# PCB.net
KiCad netlist of a schematic drawn in EAGLE
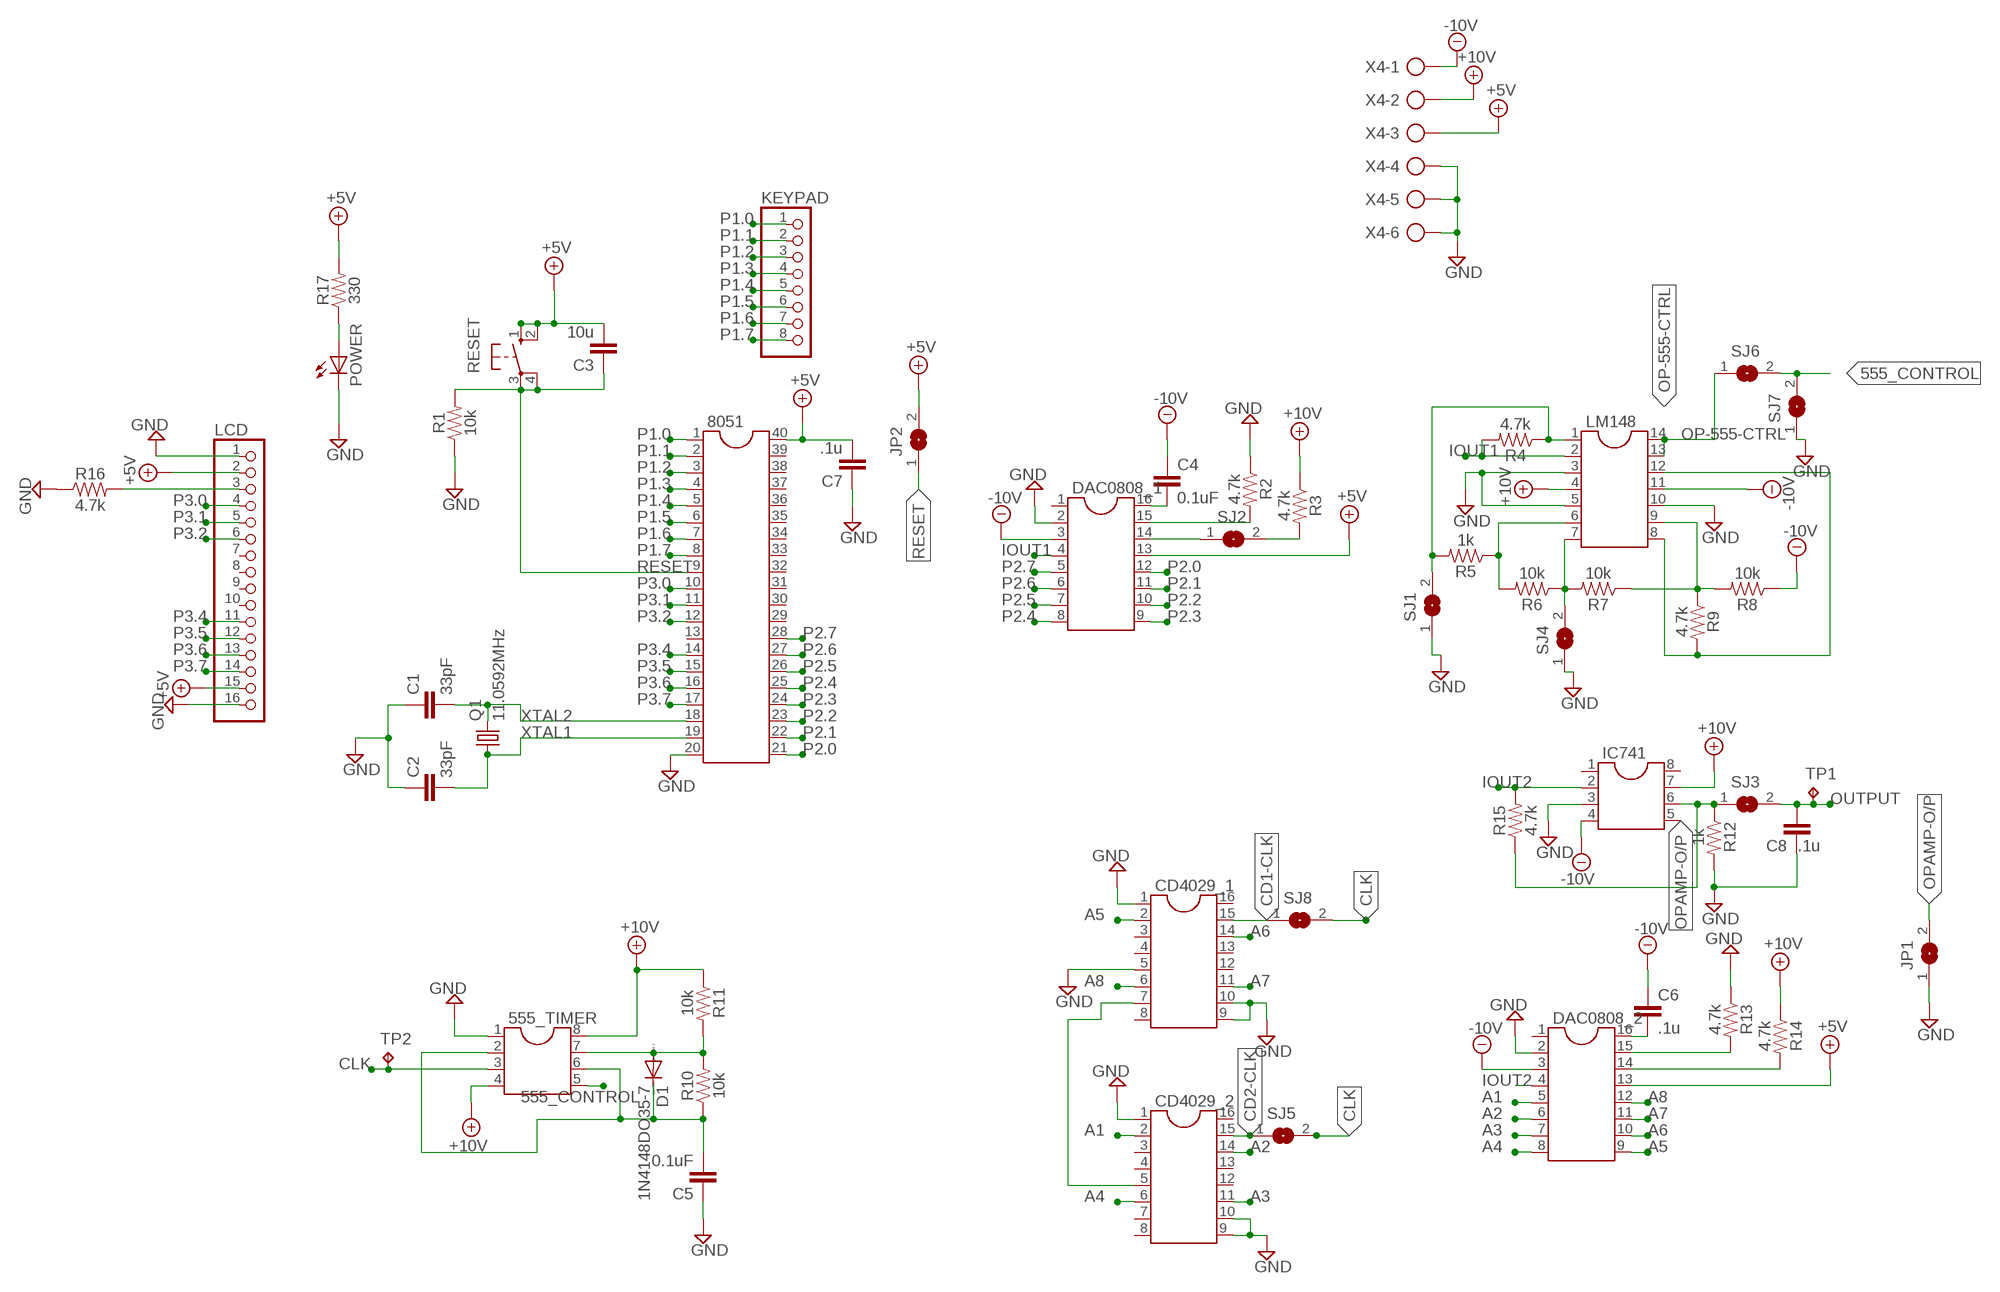
[diagram p0: schematic, sheet 1]

(export (version "E")
  (design (tool "Eeschema 10.0.6"))
  (components
    (comp (ref "555_TIMER")
      (value "DIL8")
      (footprint "eagle-import:DIL08")
      (libsource (lib "eagle-import") (part "DIL8"))
    )
    (comp (ref "8051")
      (value "DIL40")
      (footprint "eagle-import:DIL40")
      (fields (field (name "MF") "OLIMEX") (field (name "MPN") "PIC-USB-4550"))
      (libsource (lib "eagle-import") (part "DIL40"))
    )
    (comp (ref "C1")
      (value "33pF")
      (footprint "eagle-import:C025-025X050")
      (libsource (lib "eagle-import") (part "C-EU025-025X050"))
    )
    (comp (ref "C2")
      (value "33pF")
      (footprint "eagle-import:C025-025X050")
      (libsource (lib "eagle-import") (part "C-EU025-025X050"))
    )
    (comp (ref "C3")
      (value "10u")
      (footprint "eagle-import:C025-025X050")
      (libsource (lib "eagle-import") (part "C-EU025-025X050"))
    )
    (comp (ref "C4")
      (value "0.1uF")
      (footprint "eagle-import:C025-025X050")
      (libsource (lib "eagle-import") (part "C-EU025-025X050"))
    )
    (comp (ref "C5")
      (value "0.1uF")
      (footprint "eagle-import:C025-025X050")
      (libsource (lib "eagle-import") (part "C-EU025-025X050"))
    )
    (comp (ref "C6")
      (value ".1u")
      (footprint "eagle-import:C025-025X050")
      (libsource (lib "eagle-import") (part "C-EU025-025X050"))
    )
    (comp (ref "C7")
      (value ".1u")
      (footprint "eagle-import:C025-025X050")
      (libsource (lib "eagle-import") (part "C-EU025-025X050"))
    )
    (comp (ref "C8")
      (value ".1u")
      (footprint "eagle-import:C025-025X050")
      (libsource (lib "eagle-import") (part "C-EU025-025X050"))
    )
    (comp (ref "CD4029_1")
      (value "DIL16")
      (footprint "eagle-import:DIL16")
      (libsource (lib "eagle-import") (part "DIL16"))
    )
    (comp (ref "CD4029_2")
      (value "DIL16")
      (footprint "eagle-import:DIL16")
      (libsource (lib "eagle-import") (part "DIL16"))
    )
    (comp (ref "D1")
      (value "1N4148DO35-7")
      (footprint "eagle-import:DO35-7")
      (libsource (lib "eagle-import") (part "1N4148DO35-7"))
    )
    (comp (ref "DAC0808_1")
      (value "DIL16")
      (footprint "eagle-import:DIL16")
      (libsource (lib "eagle-import") (part "DIL16"))
    )
    (comp (ref "DAC0808_2")
      (value "DIL16")
      (footprint "eagle-import:DIL16")
      (libsource (lib "eagle-import") (part "DIL16"))
    )
    (comp (ref "IC741")
      (value "DIL8")
      (footprint "eagle-import:DIL08")
      (libsource (lib "eagle-import") (part "DIL8"))
    )
    (comp (ref "JP1") (value "SJ") (footprint "eagle-import:SJ") (libsource (lib "eagle-import") (part "SJ")))
    (comp (ref "JP2") (value "SJ") (footprint "eagle-import:SJ") (libsource (lib "eagle-import") (part "SJ")))
    (comp (ref "KEYPAD")
      (value "PINHD-1X8")
      (footprint "eagle-import:1X08")
      (libsource (lib "eagle-import") (part "PINHD-1X8"))
    )
    (comp (ref "LCD")
      (value "PINHD-1X16")
      (footprint "eagle-import:1X16")
      (libsource (lib "eagle-import") (part "PINHD-1X16"))
    )
    (comp (ref "LM148")
      (value "DIL14")
      (footprint "eagle-import:DIL14")
      (libsource (lib "eagle-import") (part "DIL14"))
    )
    (comp (ref "POWER")
      (value "LED5MM")
      (footprint "eagle-import:LED5MM")
      (libsource (lib "eagle-import") (part "LED5MM"))
    )
    (comp (ref "Q1")
      (value "11.0592MHz")
      (footprint "eagle-import:HC49_S")
      (fields (field (name "MF") "MULTICOMP") (field (name "MPN") "HC49SM-3.6864-30-50-60-16-ATF"))
      (libsource (lib "eagle-import") (part "CRYSTALHC49S"))
    )
    (comp (ref "R1")
      (value "10k")
      (footprint "eagle-import:AXIAL-0.3")
      (libsource (lib "eagle-import") (part "RESISTORAXIAL-0.3"))
    )
    (comp (ref "R2")
      (value "4.7k")
      (footprint "eagle-import:AXIAL-0.3")
      (libsource (lib "eagle-import") (part "RESISTORAXIAL-0.3"))
    )
    (comp (ref "R3")
      (value "4.7k")
      (footprint "eagle-import:AXIAL-0.3")
      (libsource (lib "eagle-import") (part "RESISTORAXIAL-0.3"))
    )
    (comp (ref "R4")
      (value "4.7k")
      (footprint "eagle-import:AXIAL-0.3")
      (libsource (lib "eagle-import") (part "RESISTORAXIAL-0.3"))
    )
    (comp (ref "R5")
      (value "1k")
      (footprint "eagle-import:AXIAL-0.3")
      (libsource (lib "eagle-import") (part "RESISTORAXIAL-0.3"))
    )
    (comp (ref "R6")
      (value "10k")
      (footprint "eagle-import:AXIAL-0.3")
      (libsource (lib "eagle-import") (part "RESISTORAXIAL-0.3"))
    )
    (comp (ref "R7")
      (value "10k")
      (footprint "eagle-import:AXIAL-0.3")
      (libsource (lib "eagle-import") (part "RESISTORAXIAL-0.3"))
    )
    (comp (ref "R8")
      (value "10k")
      (footprint "eagle-import:AXIAL-0.3")
      (libsource (lib "eagle-import") (part "RESISTORAXIAL-0.3"))
    )
    (comp (ref "R9")
      (value "4.7k")
      (footprint "eagle-import:AXIAL-0.3")
      (libsource (lib "eagle-import") (part "RESISTORAXIAL-0.3"))
    )
    (comp (ref "R10")
      (value "10k")
      (footprint "eagle-import:AXIAL-0.3")
      (libsource (lib "eagle-import") (part "RESISTORAXIAL-0.3"))
    )
    (comp (ref "R11")
      (value "10k")
      (footprint "eagle-import:AXIAL-0.3")
      (libsource (lib "eagle-import") (part "RESISTORAXIAL-0.3"))
    )
    (comp (ref "R12")
      (value "1k")
      (footprint "eagle-import:AXIAL-0.3")
      (libsource (lib "eagle-import") (part "RESISTORAXIAL-0.3"))
    )
    (comp (ref "R13")
      (value "4.7k")
      (footprint "eagle-import:AXIAL-0.3")
      (libsource (lib "eagle-import") (part "RESISTORAXIAL-0.3"))
    )
    (comp (ref "R14")
      (value "4.7k")
      (footprint "eagle-import:AXIAL-0.3")
      (libsource (lib "eagle-import") (part "RESISTORAXIAL-0.3"))
    )
    (comp (ref "R15")
      (value "4.7k")
      (footprint "eagle-import:AXIAL-0.3")
      (libsource (lib "eagle-import") (part "RESISTORAXIAL-0.3"))
    )
    (comp (ref "R16")
      (value "4.7k")
      (footprint "eagle-import:AXIAL-0.3")
      (libsource (lib "eagle-import") (part "RESISTORAXIAL-0.3"))
    )
    (comp (ref "R17")
      (value "330")
      (footprint "eagle-import:AXIAL-0.3")
      (libsource (lib "eagle-import") (part "RESISTORAXIAL-0.3"))
    )
    (comp (ref "RESET")
      (value "10-XX")
      (footprint "eagle-import:B3F-10XX")
      (fields (field (name "MPN") "B3F-1000") (field (name "MF") "OMRON"))
      (libsource (lib "eagle-import") (part "10-XX"))
    )
    (comp (ref "SJ1") (value "SJ") (footprint "eagle-import:SJ") (libsource (lib "eagle-import") (part "SJ")))
    (comp (ref "SJ2") (value "SJ") (footprint "eagle-import:SJ") (libsource (lib "eagle-import") (part "SJ")))
    (comp (ref "SJ3") (value "SJ") (footprint "eagle-import:SJ") (libsource (lib "eagle-import") (part "SJ")))
    (comp (ref "SJ4") (value "SJ") (footprint "eagle-import:SJ") (libsource (lib "eagle-import") (part "SJ")))
    (comp (ref "SJ5") (value "SJ") (footprint "eagle-import:SJ") (libsource (lib "eagle-import") (part "SJ")))
    (comp (ref "SJ6") (value "SJ") (footprint "eagle-import:SJ") (libsource (lib "eagle-import") (part "SJ")))
    (comp (ref "SJ7") (value "SJ") (footprint "eagle-import:SJ") (libsource (lib "eagle-import") (part "SJ")))
    (comp (ref "SJ8") (value "SJ") (footprint "eagle-import:SJ") (libsource (lib "eagle-import") (part "SJ")))
    (comp (ref "TP1")
      (value "TPPAD1-20")
      (footprint "eagle-import:P1-20")
      (libsource (lib "eagle-import") (part "TPPAD1-20"))
    )
    (comp (ref "TP2")
      (value "TPPAD1-20")
      (footprint "eagle-import:P1-20")
      (libsource (lib "eagle-import") (part "TPPAD1-20"))
    )
    (comp (ref "X4")
      (value "AK500/6-H")
      (footprint "eagle-import:AK500_6-H")
      (fields (field (name "OC_FARNELL") "unknown"))
      (libsource (lib "eagle-import") (part "AK500/6-H"))
    )
  )
  (nets
    (net (code "1") (name "+5V") (class "Default")
      (node (ref "8051") (pin "40") (pinfunction "40_40") (pintype "passive"))
      (node (ref "C3") (pin "2") (pinfunction "2_2") (pintype "passive"))
      (node (ref "C7") (pin "2") (pinfunction "2_2") (pintype "passive"))
      (node (ref "DAC0808_1") (pin "13") (pinfunction "13_13") (pintype "passive"))
      (node (ref "DAC0808_2") (pin "13") (pinfunction "13_13") (pintype "passive"))
      (node (ref "JP2") (pin "2") (pinfunction "2_2") (pintype "passive"))
      (node (ref "LCD") (pin "15") (pinfunction "15_15") (pintype "passive"))
      (node (ref "LCD") (pin "2") (pinfunction "2_2") (pintype "passive"))
      (node (ref "R17") (pin "P$2") (pinfunction "2_P$2") (pintype "passive"))
      (node (ref "RESET") (pin "1") (pinfunction "S_1") (pintype "passive"))
      (node (ref "RESET") (pin "2") (pinfunction "S1_2") (pintype "passive"))
      (node (ref "X4") (pin "3") (pinfunction "KL_3") (pintype "passive"))
    )
    (net (code "2") (name "+10V") (class "Default")
      (node (ref "555_TIMER") (pin "4") (pinfunction "4_4") (pintype "passive"))
      (node (ref "555_TIMER") (pin "8") (pinfunction "8_8") (pintype "passive"))
      (node (ref "IC741") (pin "7") (pinfunction "7_7") (pintype "passive"))
      (node (ref "LM148") (pin "4") (pinfunction "4_4") (pintype "passive"))
      (node (ref "R11") (pin "P$1") (pinfunction "1_P$1") (pintype "passive"))
      (node (ref "R14") (pin "P$1") (pinfunction "1_P$1") (pintype "passive"))
      (node (ref "R3") (pin "P$1") (pinfunction "1_P$1") (pintype "passive"))
      (node (ref "X4") (pin "2") (pinfunction "KL_2") (pintype "passive"))
    )
    (net (code "3") (name "-10V") (class "Default")
      (node (ref "C4") (pin "1") (pinfunction "1_1") (pintype "passive"))
      (node (ref "C6") (pin "1") (pinfunction "1_1") (pintype "passive"))
      (node (ref "DAC0808_1") (pin "3") (pinfunction "3_3") (pintype "passive"))
      (node (ref "DAC0808_2") (pin "3") (pinfunction "3_3") (pintype "passive"))
      (node (ref "IC741") (pin "4") (pinfunction "4_4") (pintype "passive"))
      (node (ref "LM148") (pin "11") (pinfunction "11_11") (pintype "passive"))
      (node (ref "R8") (pin "P$1") (pinfunction "1_P$1") (pintype "passive"))
      (node (ref "X4") (pin "1") (pinfunction "KL_1") (pintype "passive"))
    )
    (net (code "4") (name "/A1") (class "Default")
      (node (ref "CD4029_2") (pin "2") (pinfunction "2_2") (pintype "passive"))
      (node (ref "DAC0808_2") (pin "5") (pinfunction "5_5") (pintype "passive"))
    )
    (net (code "5") (name "/A2") (class "Default")
      (node (ref "CD4029_2") (pin "14") (pinfunction "14_14") (pintype "passive"))
      (node (ref "DAC0808_2") (pin "6") (pinfunction "6_6") (pintype "passive"))
    )
    (net (code "6") (name "/A3") (class "Default")
      (node (ref "CD4029_2") (pin "11") (pinfunction "11_11") (pintype "passive"))
      (node (ref "DAC0808_2") (pin "7") (pinfunction "7_7") (pintype "passive"))
    )
    (net (code "7") (name "/A4") (class "Default")
      (node (ref "CD4029_2") (pin "6") (pinfunction "6_6") (pintype "passive"))
      (node (ref "DAC0808_2") (pin "8") (pinfunction "8_8") (pintype "passive"))
    )
    (net (code "8") (name "/A5") (class "Default")
      (node (ref "CD4029_1") (pin "2") (pinfunction "2_2") (pintype "passive"))
      (node (ref "DAC0808_2") (pin "9") (pinfunction "9_9") (pintype "passive"))
    )
    (net (code "9") (name "/A6") (class "Default")
      (node (ref "CD4029_1") (pin "14") (pinfunction "14_14") (pintype "passive"))
      (node (ref "DAC0808_2") (pin "10") (pinfunction "10_10") (pintype "passive"))
    )
    (net (code "10") (name "/A7") (class "Default")
      (node (ref "CD4029_1") (pin "11") (pinfunction "11_11") (pintype "passive"))
      (node (ref "DAC0808_2") (pin "11") (pinfunction "11_11") (pintype "passive"))
    )
    (net (code "11") (name "/A8") (class "Default")
      (node (ref "CD4029_1") (pin "6") (pinfunction "6_6") (pintype "passive"))
      (node (ref "DAC0808_2") (pin "12") (pinfunction "12_12") (pintype "passive"))
    )
    (net (code "12") (name "/IOUT1") (class "Default")
      (node (ref "DAC0808_1") (pin "4") (pinfunction "4_4") (pintype "passive"))
      (node (ref "LM148") (pin "2") (pinfunction "2_2") (pintype "passive"))
      (node (ref "R4") (pin "P$2") (pinfunction "2_P$2") (pintype "passive"))
    )
    (net (code "13") (name "/IOUT2") (class "Default")
      (node (ref "DAC0808_2") (pin "4") (pinfunction "4_4") (pintype "passive"))
      (node (ref "IC741") (pin "2") (pinfunction "2_2") (pintype "passive"))
      (node (ref "R15") (pin "P$2") (pinfunction "2_P$2") (pintype "passive"))
    )
    (net (code "14") (name "/OUTPUT") (class "Default")
      (node (ref "C8") (pin "2") (pinfunction "2_2") (pintype "passive"))
      (node (ref "SJ3") (pin "2") (pinfunction "2_2") (pintype "passive"))
      (node (ref "TP1") (pin "TP") (pinfunction "TP_TP") (pintype "input"))
    )
    (net (code "15") (name "/P1.0") (class "Default")
      (node (ref "8051") (pin "1") (pinfunction "1_1") (pintype "passive"))
      (node (ref "KEYPAD") (pin "1") (pinfunction "1_1") (pintype "passive"))
    )
    (net (code "16") (name "/P1.1") (class "Default")
      (node (ref "8051") (pin "2") (pinfunction "2_2") (pintype "passive"))
      (node (ref "KEYPAD") (pin "2") (pinfunction "2_2") (pintype "passive"))
    )
    (net (code "17") (name "/P1.2") (class "Default")
      (node (ref "8051") (pin "3") (pinfunction "3_3") (pintype "passive"))
      (node (ref "KEYPAD") (pin "3") (pinfunction "3_3") (pintype "passive"))
    )
    (net (code "18") (name "/P1.3") (class "Default")
      (node (ref "8051") (pin "4") (pinfunction "4_4") (pintype "passive"))
      (node (ref "KEYPAD") (pin "4") (pinfunction "4_4") (pintype "passive"))
    )
    (net (code "19") (name "/P1.4") (class "Default")
      (node (ref "8051") (pin "5") (pinfunction "5_5") (pintype "passive"))
      (node (ref "KEYPAD") (pin "5") (pinfunction "5_5") (pintype "passive"))
    )
    (net (code "20") (name "/P1.5") (class "Default")
      (node (ref "8051") (pin "6") (pinfunction "6_6") (pintype "passive"))
      (node (ref "KEYPAD") (pin "6") (pinfunction "6_6") (pintype "passive"))
    )
    (net (code "21") (name "/P1.6") (class "Default")
      (node (ref "8051") (pin "7") (pinfunction "7_7") (pintype "passive"))
      (node (ref "KEYPAD") (pin "7") (pinfunction "7_7") (pintype "passive"))
    )
    (net (code "22") (name "/P1.7") (class "Default")
      (node (ref "8051") (pin "8") (pinfunction "8_8") (pintype "passive"))
      (node (ref "KEYPAD") (pin "8") (pinfunction "8_8") (pintype "passive"))
    )
    (net (code "23") (name "/P2.0") (class "Default")
      (node (ref "8051") (pin "21") (pinfunction "21_21") (pintype "passive"))
      (node (ref "DAC0808_1") (pin "12") (pinfunction "12_12") (pintype "passive"))
    )
    (net (code "24") (name "/P2.1") (class "Default")
      (node (ref "8051") (pin "22") (pinfunction "22_22") (pintype "passive"))
      (node (ref "DAC0808_1") (pin "11") (pinfunction "11_11") (pintype "passive"))
    )
    (net (code "25") (name "/P2.2") (class "Default")
      (node (ref "8051") (pin "23") (pinfunction "23_23") (pintype "passive"))
      (node (ref "DAC0808_1") (pin "10") (pinfunction "10_10") (pintype "passive"))
    )
    (net (code "26") (name "/P2.3") (class "Default")
      (node (ref "8051") (pin "24") (pinfunction "24_24") (pintype "passive"))
      (node (ref "DAC0808_1") (pin "9") (pinfunction "9_9") (pintype "passive"))
    )
    (net (code "27") (name "/P2.4") (class "Default")
      (node (ref "8051") (pin "25") (pinfunction "25_25") (pintype "passive"))
      (node (ref "DAC0808_1") (pin "8") (pinfunction "8_8") (pintype "passive"))
    )
    (net (code "28") (name "/P2.5") (class "Default")
      (node (ref "8051") (pin "26") (pinfunction "26_26") (pintype "passive"))
      (node (ref "DAC0808_1") (pin "7") (pinfunction "7_7") (pintype "passive"))
    )
    (net (code "29") (name "/P2.6") (class "Default")
      (node (ref "8051") (pin "27") (pinfunction "27_27") (pintype "passive"))
      (node (ref "DAC0808_1") (pin "6") (pinfunction "6_6") (pintype "passive"))
    )
    (net (code "30") (name "/P2.7") (class "Default")
      (node (ref "8051") (pin "28") (pinfunction "28_28") (pintype "passive"))
      (node (ref "DAC0808_1") (pin "5") (pinfunction "5_5") (pintype "passive"))
    )
    (net (code "31") (name "/P3.0") (class "Default")
      (node (ref "8051") (pin "10") (pinfunction "10_10") (pintype "passive"))
      (node (ref "LCD") (pin "4") (pinfunction "4_4") (pintype "passive"))
    )
    (net (code "32") (name "/P3.1") (class "Default")
      (node (ref "8051") (pin "11") (pinfunction "11_11") (pintype "passive"))
      (node (ref "LCD") (pin "5") (pinfunction "5_5") (pintype "passive"))
    )
    (net (code "33") (name "/P3.2") (class "Default")
      (node (ref "8051") (pin "12") (pinfunction "12_12") (pintype "passive"))
      (node (ref "LCD") (pin "6") (pinfunction "6_6") (pintype "passive"))
    )
    (net (code "34") (name "/P3.4") (class "Default")
      (node (ref "8051") (pin "14") (pinfunction "14_14") (pintype "passive"))
      (node (ref "LCD") (pin "11") (pinfunction "11_11") (pintype "passive"))
    )
    (net (code "35") (name "/P3.5") (class "Default")
      (node (ref "8051") (pin "15") (pinfunction "15_15") (pintype "passive"))
      (node (ref "LCD") (pin "12") (pinfunction "12_12") (pintype "passive"))
    )
    (net (code "36") (name "/P3.6") (class "Default")
      (node (ref "8051") (pin "16") (pinfunction "16_16") (pintype "passive"))
      (node (ref "LCD") (pin "13") (pinfunction "13_13") (pintype "passive"))
    )
    (net (code "37") (name "/P3.7") (class "Default")
      (node (ref "8051") (pin "17") (pinfunction "17_17") (pintype "passive"))
      (node (ref "LCD") (pin "14") (pinfunction "14_14") (pintype "passive"))
    )
    (net (code "38") (name "/XTAL1") (class "Default")
      (node (ref "8051") (pin "19") (pinfunction "19_19") (pintype "passive"))
      (node (ref "C2") (pin "2") (pinfunction "2_2") (pintype "passive"))
      (node (ref "Q1") (pin "1") (pinfunction "1_1") (pintype "passive"))
    )
    (net (code "39") (name "/XTAL2") (class "Default")
      (node (ref "8051") (pin "18") (pinfunction "18_18") (pintype "passive"))
      (node (ref "C1") (pin "2") (pinfunction "2_2") (pintype "passive"))
      (node (ref "Q1") (pin "2") (pinfunction "2_2") (pintype "passive"))
    )
    (net (code "40") (name "555_CONTROL") (class "Default")
      (node (ref "555_TIMER") (pin "5") (pinfunction "5_5") (pintype "passive"))
      (node (ref "SJ6") (pin "2") (pinfunction "2_2") (pintype "passive"))
      (node (ref "SJ7") (pin "2") (pinfunction "2_2") (pintype "passive"))
    )
    (net (code "41") (name "CD1-CLK") (class "Default")
      (node (ref "CD4029_1") (pin "15") (pinfunction "15_15") (pintype "passive"))
      (node (ref "SJ8") (pin "1") (pinfunction "1_1") (pintype "passive"))
    )
    (net (code "42") (name "CD2-CLK") (class "Default")
      (node (ref "CD4029_2") (pin "15") (pinfunction "15_15") (pintype "passive"))
      (node (ref "SJ5") (pin "1") (pinfunction "1_1") (pintype "passive"))
    )
    (net (code "43") (name "CLK") (class "Default")
      (node (ref "555_TIMER") (pin "3") (pinfunction "3_3") (pintype "passive"))
      (node (ref "SJ5") (pin "2") (pinfunction "2_2") (pintype "passive"))
      (node (ref "SJ8") (pin "2") (pinfunction "2_2") (pintype "passive"))
      (node (ref "TP2") (pin "TP") (pinfunction "TP_TP") (pintype "input"))
    )
    (net (code "44") (name "GND") (class "Default")
      (node (ref "555_TIMER") (pin "1") (pinfunction "1_1") (pintype "passive"))
      (node (ref "8051") (pin "20") (pinfunction "20_20") (pintype "passive"))
      (node (ref "C1") (pin "1") (pinfunction "1_1") (pintype "passive"))
      (node (ref "C2") (pin "1") (pinfunction "1_1") (pintype "passive"))
      (node (ref "C5") (pin "1") (pinfunction "1_1") (pintype "passive"))
      (node (ref "C7") (pin "1") (pinfunction "1_1") (pintype "passive"))
      (node (ref "C8") (pin "1") (pinfunction "1_1") (pintype "passive"))
      (node (ref "CD4029_1") (pin "1") (pinfunction "1_1") (pintype "passive"))
      (node (ref "CD4029_1") (pin "10") (pinfunction "10_10") (pintype "passive"))
      (node (ref "CD4029_1") (pin "5") (pinfunction "5_5") (pintype "passive"))
      (node (ref "CD4029_1") (pin "9") (pinfunction "9_9") (pintype "passive"))
      (node (ref "CD4029_2") (pin "1") (pinfunction "1_1") (pintype "passive"))
      (node (ref "CD4029_2") (pin "10") (pinfunction "10_10") (pintype "passive"))
      (node (ref "CD4029_2") (pin "9") (pinfunction "9_9") (pintype "passive"))
      (node (ref "DAC0808_1") (pin "2") (pinfunction "2_2") (pintype "passive"))
      (node (ref "DAC0808_2") (pin "2") (pinfunction "2_2") (pintype "passive"))
      (node (ref "IC741") (pin "3") (pinfunction "3_3") (pintype "passive"))
      (node (ref "JP1") (pin "1") (pinfunction "1_1") (pintype "passive"))
      (node (ref "LCD") (pin "1") (pinfunction "1_1") (pintype "passive"))
      (node (ref "LCD") (pin "16") (pinfunction "16_16") (pintype "passive"))
      (node (ref "LM148") (pin "10") (pinfunction "10_10") (pintype "passive"))
      (node (ref "LM148") (pin "3") (pinfunction "3_3") (pintype "passive"))
      (node (ref "LM148") (pin "5") (pinfunction "5_5") (pintype "passive"))
      (node (ref "POWER") (pin "K") (pinfunction "C_K") (pintype "passive"))
      (node (ref "R1") (pin "P$1") (pinfunction "1_P$1") (pintype "passive"))
      (node (ref "R12") (pin "P$2") (pinfunction "2_P$2") (pintype "passive"))
      (node (ref "R13") (pin "P$1") (pinfunction "1_P$1") (pintype "passive"))
      (node (ref "R16") (pin "P$1") (pinfunction "1_P$1") (pintype "passive"))
      (node (ref "R2") (pin "P$1") (pinfunction "1_P$1") (pintype "passive"))
      (node (ref "SJ1") (pin "1") (pinfunction "1_1") (pintype "passive"))
      (node (ref "SJ4") (pin "1") (pinfunction "1_1") (pintype "passive"))
      (node (ref "SJ7") (pin "1") (pinfunction "1_1") (pintype "passive"))
      (node (ref "X4") (pin "4") (pinfunction "KL_4") (pintype "passive"))
      (node (ref "X4") (pin "5") (pinfunction "KL_5") (pintype "passive"))
      (node (ref "X4") (pin "6") (pinfunction "KL_6") (pintype "passive"))
    )
    (net (code "45") (name "Net-(C4-Pad2)") (class "Default")
      (node (ref "C4") (pin "2") (pinfunction "2_2") (pintype "passive"))
      (node (ref "DAC0808_1") (pin "16") (pinfunction "16_16") (pintype "passive"))
    )
    (net (code "46") (name "Net-(C6-Pad2)") (class "Default")
      (node (ref "C6") (pin "2") (pinfunction "2_2") (pintype "passive"))
      (node (ref "DAC0808_2") (pin "16") (pinfunction "16_16") (pintype "passive"))
    )
    (net (code "47") (name "Net-(CD4029_1-Pad7)") (class "Default")
      (node (ref "CD4029_1") (pin "7") (pinfunction "7_7") (pintype "passive"))
      (node (ref "CD4029_2") (pin "5") (pinfunction "5_5") (pintype "passive"))
    )
    (net (code "48") (name "Net-(DAC0808_1-Pad14)") (class "Default")
      (node (ref "DAC0808_1") (pin "14") (pinfunction "14_14") (pintype "passive"))
      (node (ref "SJ2") (pin "1") (pinfunction "1_1") (pintype "passive"))
    )
    (net (code "49") (name "Net-(R2-2)") (class "Default")
      (node (ref "DAC0808_1") (pin "15") (pinfunction "15_15") (pintype "passive"))
      (node (ref "R2") (pin "P$2") (pinfunction "2_P$2") (pintype "passive"))
    )
    (net (code "50") (name "Net-(R3-2)") (class "Default")
      (node (ref "R3") (pin "P$2") (pinfunction "2_P$2") (pintype "passive"))
      (node (ref "SJ2") (pin "2") (pinfunction "2_2") (pintype "passive"))
    )
    (net (code "51") (name "Net-(R4-1)") (class "Default")
      (node (ref "LM148") (pin "1") (pinfunction "1_1") (pintype "passive"))
      (node (ref "R4") (pin "P$1") (pinfunction "1_P$1") (pintype "passive"))
      (node (ref "R5") (pin "P$2") (pinfunction "2_P$2") (pintype "passive"))
      (node (ref "SJ1") (pin "2") (pinfunction "2_2") (pintype "passive"))
    )
    (net (code "52") (name "Net-(R5-1)") (class "Default")
      (node (ref "LM148") (pin "6") (pinfunction "6_6") (pintype "passive"))
      (node (ref "R5") (pin "P$1") (pinfunction "1_P$1") (pintype "passive"))
      (node (ref "R6") (pin "P$2") (pinfunction "2_P$2") (pintype "passive"))
    )
    (net (code "53") (name "Net-(R6-1)") (class "Default")
      (node (ref "LM148") (pin "7") (pinfunction "7_7") (pintype "passive"))
      (node (ref "R6") (pin "P$1") (pinfunction "1_P$1") (pintype "passive"))
      (node (ref "R7") (pin "P$2") (pinfunction "2_P$2") (pintype "passive"))
      (node (ref "SJ4") (pin "2") (pinfunction "2_2") (pintype "passive"))
    )
    (net (code "54") (name "Net-(R7-1)") (class "Default")
      (node (ref "LM148") (pin "9") (pinfunction "9_9") (pintype "passive"))
      (node (ref "R7") (pin "P$1") (pinfunction "1_P$1") (pintype "passive"))
      (node (ref "R8") (pin "P$2") (pinfunction "2_P$2") (pintype "passive"))
      (node (ref "R9") (pin "P$1") (pinfunction "1_P$1") (pintype "passive"))
    )
    (net (code "55") (name "Net-(R9-2)") (class "Default")
      (node (ref "LM148") (pin "12") (pinfunction "12_12") (pintype "passive"))
      (node (ref "LM148") (pin "8") (pinfunction "8_8") (pintype "passive"))
      (node (ref "R9") (pin "P$2") (pinfunction "2_P$2") (pintype "passive"))
    )
    (net (code "56") (name "Net-(R10-1)") (class "Default")
      (node (ref "555_TIMER") (pin "2") (pinfunction "2_2") (pintype "passive"))
      (node (ref "555_TIMER") (pin "6") (pinfunction "6_6") (pintype "passive"))
      (node (ref "C5") (pin "2") (pinfunction "2_2") (pintype "passive"))
      (node (ref "D1") (pin "C") (pinfunction "C_C") (pintype "passive"))
      (node (ref "R10") (pin "P$1") (pinfunction "1_P$1") (pintype "passive"))
    )
    (net (code "57") (name "Net-(R10-2)") (class "Default")
      (node (ref "555_TIMER") (pin "7") (pinfunction "7_7") (pintype "passive"))
      (node (ref "D1") (pin "A") (pinfunction "A_A") (pintype "passive"))
      (node (ref "R10") (pin "P$2") (pinfunction "2_P$2") (pintype "passive"))
      (node (ref "R11") (pin "P$2") (pinfunction "2_P$2") (pintype "passive"))
    )
    (net (code "58") (name "Net-(R13-2)") (class "Default")
      (node (ref "DAC0808_2") (pin "15") (pinfunction "15_15") (pintype "passive"))
      (node (ref "R13") (pin "P$2") (pinfunction "2_P$2") (pintype "passive"))
    )
    (net (code "59") (name "Net-(R14-2)") (class "Default")
      (node (ref "DAC0808_2") (pin "14") (pinfunction "14_14") (pintype "passive"))
      (node (ref "R14") (pin "P$2") (pinfunction "2_P$2") (pintype "passive"))
    )
    (net (code "60") (name "Net-(R16-2)") (class "Default")
      (node (ref "LCD") (pin "3") (pinfunction "3_3") (pintype "passive"))
      (node (ref "R16") (pin "P$2") (pinfunction "2_P$2") (pintype "passive"))
    )
    (net (code "61") (name "Net-(R17-1)") (class "Default")
      (node (ref "POWER") (pin "A") (pinfunction "A_A") (pintype "passive"))
      (node (ref "R17") (pin "P$1") (pinfunction "1_P$1") (pintype "passive"))
    )
    (net (code "62") (name "OP-555-CTRL") (class "Default")
      (node (ref "LM148") (pin "13") (pinfunction "13_13") (pintype "passive"))
      (node (ref "LM148") (pin "14") (pinfunction "14_14") (pintype "passive"))
      (node (ref "SJ6") (pin "1") (pinfunction "1_1") (pintype "passive"))
    )
    (net (code "63") (name "OPAMP-O{slash}P") (class "Default")
      (node (ref "IC741") (pin "6") (pinfunction "6_6") (pintype "passive"))
      (node (ref "JP1") (pin "2") (pinfunction "2_2") (pintype "passive"))
      (node (ref "R12") (pin "P$1") (pinfunction "1_P$1") (pintype "passive"))
      (node (ref "R15") (pin "P$1") (pinfunction "1_P$1") (pintype "passive"))
      (node (ref "SJ3") (pin "1") (pinfunction "1_1") (pintype "passive"))
    )
    (net (code "64") (name "RESET") (class "Default")
      (node (ref "8051") (pin "9") (pinfunction "9_9") (pintype "passive"))
      (node (ref "C3") (pin "1") (pinfunction "1_1") (pintype "passive"))
      (node (ref "JP2") (pin "1") (pinfunction "1_1") (pintype "passive"))
      (node (ref "R1") (pin "P$2") (pinfunction "2_P$2") (pintype "passive"))
      (node (ref "RESET") (pin "3") (pinfunction "P_3") (pintype "passive"))
      (node (ref "RESET") (pin "4") (pinfunction "P1_4") (pintype "passive"))
    )
    (net (code "65") (name "unconnected-(8051-Pad13)") (class "Default")
      (node (ref "8051") (pin "13") (pinfunction "13_13") (pintype "passive"))
    )
    (net (code "66") (name "unconnected-(8051-Pad29)") (class "Default")
      (node (ref "8051") (pin "29") (pinfunction "29_29") (pintype "passive"))
    )
    (net (code "67") (name "unconnected-(8051-Pad30)") (class "Default")
      (node (ref "8051") (pin "30") (pinfunction "30_30") (pintype "passive"))
    )
    (net (code "68") (name "unconnected-(8051-Pad31)") (class "Default")
      (node (ref "8051") (pin "31") (pinfunction "31_31") (pintype "passive"))
    )
    (net (code "69") (name "unconnected-(8051-Pad32)") (class "Default")
      (node (ref "8051") (pin "32") (pinfunction "32_32") (pintype "passive"))
    )
    (net (code "70") (name "unconnected-(8051-Pad33)") (class "Default")
      (node (ref "8051") (pin "33") (pinfunction "33_33") (pintype "passive"))
    )
    (net (code "71") (name "unconnected-(8051-Pad34)") (class "Default")
      (node (ref "8051") (pin "34") (pinfunction "34_34") (pintype "passive"))
    )
    (net (code "72") (name "unconnected-(8051-Pad35)") (class "Default")
      (node (ref "8051") (pin "35") (pinfunction "35_35") (pintype "passive"))
    )
    (net (code "73") (name "unconnected-(8051-Pad36)") (class "Default")
      (node (ref "8051") (pin "36") (pinfunction "36_36") (pintype "passive"))
    )
    (net (code "74") (name "unconnected-(8051-Pad37)") (class "Default")
      (node (ref "8051") (pin "37") (pinfunction "37_37") (pintype "passive"))
    )
    (net (code "75") (name "unconnected-(8051-Pad38)") (class "Default")
      (node (ref "8051") (pin "38") (pinfunction "38_38") (pintype "passive"))
    )
    (net (code "76") (name "unconnected-(8051-Pad39)") (class "Default")
      (node (ref "8051") (pin "39") (pinfunction "39_39") (pintype "passive"))
    )
    (net (code "77") (name "unconnected-(CD4029_1-Pad3)") (class "Default")
      (node (ref "CD4029_1") (pin "3") (pinfunction "3_3") (pintype "passive"))
    )
    (net (code "78") (name "unconnected-(CD4029_1-Pad4)") (class "Default")
      (node (ref "CD4029_1") (pin "4") (pinfunction "4_4") (pintype "passive"))
    )
    (net (code "79") (name "unconnected-(CD4029_1-Pad8)") (class "Default")
      (node (ref "CD4029_1") (pin "8") (pinfunction "8_8") (pintype "passive"))
    )
    (net (code "80") (name "unconnected-(CD4029_1-Pad12)") (class "Default")
      (node (ref "CD4029_1") (pin "12") (pinfunction "12_12") (pintype "passive"))
    )
    (net (code "81") (name "unconnected-(CD4029_1-Pad13)") (class "Default")
      (node (ref "CD4029_1") (pin "13") (pinfunction "13_13") (pintype "passive"))
    )
    (net (code "82") (name "unconnected-(CD4029_1-Pad16)") (class "Default")
      (node (ref "CD4029_1") (pin "16") (pinfunction "16_16") (pintype "passive"))
    )
    (net (code "83") (name "unconnected-(CD4029_2-Pad3)") (class "Default")
      (node (ref "CD4029_2") (pin "3") (pinfunction "3_3") (pintype "passive"))
    )
    (net (code "84") (name "unconnected-(CD4029_2-Pad4)") (class "Default")
      (node (ref "CD4029_2") (pin "4") (pinfunction "4_4") (pintype "passive"))
    )
    (net (code "85") (name "unconnected-(CD4029_2-Pad7)") (class "Default")
      (node (ref "CD4029_2") (pin "7") (pinfunction "7_7") (pintype "passive"))
    )
    (net (code "86") (name "unconnected-(CD4029_2-Pad8)") (class "Default")
      (node (ref "CD4029_2") (pin "8") (pinfunction "8_8") (pintype "passive"))
    )
    (net (code "87") (name "unconnected-(CD4029_2-Pad12)") (class "Default")
      (node (ref "CD4029_2") (pin "12") (pinfunction "12_12") (pintype "passive"))
    )
    (net (code "88") (name "unconnected-(CD4029_2-Pad13)") (class "Default")
      (node (ref "CD4029_2") (pin "13") (pinfunction "13_13") (pintype "passive"))
    )
    (net (code "89") (name "unconnected-(CD4029_2-Pad16)") (class "Default")
      (node (ref "CD4029_2") (pin "16") (pinfunction "16_16") (pintype "passive"))
    )
    (net (code "90") (name "unconnected-(DAC0808_1-Pad1)") (class "Default")
      (node (ref "DAC0808_1") (pin "1") (pinfunction "1_1") (pintype "passive"))
    )
    (net (code "91") (name "unconnected-(DAC0808_2-Pad1)") (class "Default")
      (node (ref "DAC0808_2") (pin "1") (pinfunction "1_1") (pintype "passive"))
    )
    (net (code "92") (name "unconnected-(IC741-Pad1)") (class "Default")
      (node (ref "IC741") (pin "1") (pinfunction "1_1") (pintype "passive"))
    )
    (net (code "93") (name "unconnected-(IC741-Pad5)") (class "Default")
      (node (ref "IC741") (pin "5") (pinfunction "5_5") (pintype "passive"))
    )
    (net (code "94") (name "unconnected-(IC741-Pad8)") (class "Default")
      (node (ref "IC741") (pin "8") (pinfunction "8_8") (pintype "passive"))
    )
    (net (code "95") (name "unconnected-(LCD-Pad7)") (class "Default")
      (node (ref "LCD") (pin "7") (pinfunction "7_7") (pintype "passive"))
    )
    (net (code "96") (name "unconnected-(LCD-Pad8)") (class "Default")
      (node (ref "LCD") (pin "8") (pinfunction "8_8") (pintype "passive"))
    )
    (net (code "97") (name "unconnected-(LCD-Pad9)") (class "Default")
      (node (ref "LCD") (pin "9") (pinfunction "9_9") (pintype "passive"))
    )
    (net (code "98") (name "unconnected-(LCD-Pad10)") (class "Default")
      (node (ref "LCD") (pin "10") (pinfunction "10_10") (pintype "passive"))
    )
  )
)
